# ModulatedIRSensor.net
KiCad netlist of a schematic drawn in EAGLE
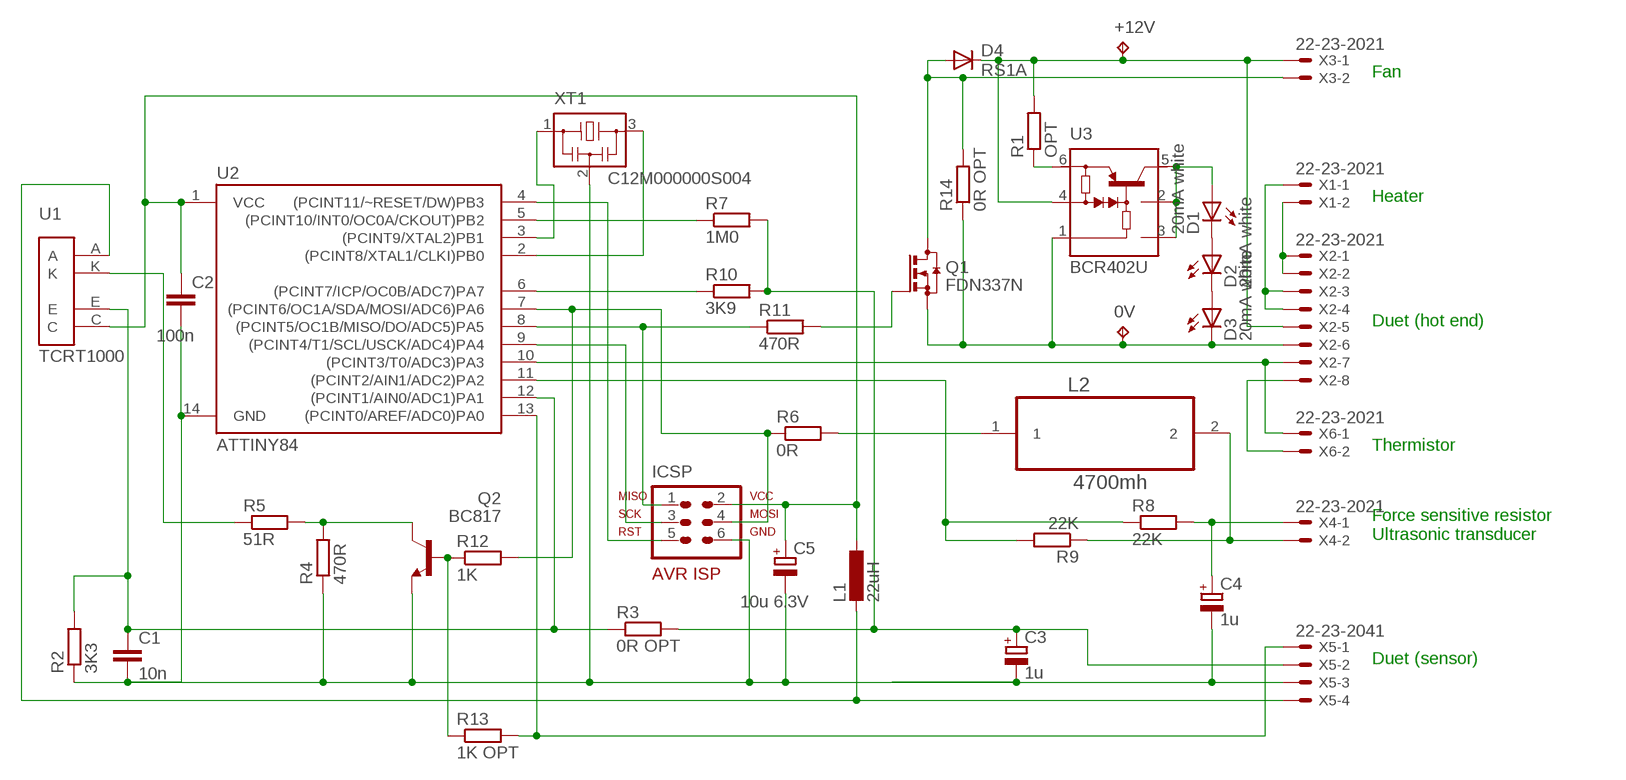
[diagram p0: schematic, sheet 1]

(export (version "E")
  (design (tool "Eeschema 10.0.6"))
  (components
    (comp (ref "+12V")
      (value "TPPAD1-13")
      (footprint "eagle-import:P1-13")
      (libsource (lib "eagle-import") (part "TPPAD1-13"))
    )
    (comp (ref "0V")
      (value "TPPAD1-13")
      (footprint "eagle-import:P1-13")
      (libsource (lib "eagle-import") (part "TPPAD1-13"))
    )
    (comp (ref "C1")
      (value "10n")
      (footprint "eagle-import:C0603")
      (libsource (lib "eagle-import") (part "C-EUC0603"))
    )
    (comp (ref "C2")
      (value "100n")
      (footprint "eagle-import:C0603")
      (libsource (lib "eagle-import") (part "C-EUC0603"))
    )
    (comp (ref "C3")
      (value "1u")
      (footprint "eagle-import:SMC_A")
      (libsource (lib "eagle-import") (part "resistor_CPOL-EUSMCA"))
    )
    (comp (ref "C4")
      (value "1u")
      (footprint "eagle-import:SMC_A")
      (libsource (lib "eagle-import") (part "resistor_CPOL-EUSMCA"))
    )
    (comp (ref "C5")
      (value "10u 6.3V")
      (footprint "eagle-import:SMC_A")
      (libsource (lib "eagle-import") (part "CPOL-EUSMCA"))
    )
    (comp (ref "D1")
      (value "20mA white")
      (footprint "eagle-import:LED5MM")
      (libsource (lib "eagle-import") (part "LED5MM"))
    )
    (comp (ref "D2")
      (value "20mA white")
      (footprint "eagle-import:LED5MM")
      (libsource (lib "eagle-import") (part "LED5MM"))
    )
    (comp (ref "D3")
      (value "20mA white")
      (footprint "eagle-import:LED5MM")
      (libsource (lib "eagle-import") (part "LED5MM"))
    )
    (comp (ref "D4")
      (value "RS1A")
      (footprint "eagle-import:DO214AC")
      (libsource (lib "eagle-import") (part "DIODE-DO214AC"))
    )
    (comp (ref "ICSP")
      (value "AVR-ISP-6VERT")
      (footprint "eagle-import:AVR-ISP-6")
      (libsource (lib "eagle-import") (part "AVR-ISP-6VERT"))
    )
    (comp (ref "L1")
      (value "22uH")
      (footprint "eagle-import:L2012C")
      (libsource (lib "eagle-import") (part "L-EUL2012C"))
    )
    (comp (ref "L2")
      (value "4700mh")
      (footprint "eagle-import:INDC5650X530N")
      (fields (field (name "MPN") "B82442H1475K") (field (name "TOLERANCE") "±10%"))
      (libsource (lib "eagle-import") (part "B82442H1475K"))
    )
    (comp (ref "Q1")
      (value "FDN337N")
      (footprint "eagle-import:SOT23")
      (libsource (lib "eagle-import") (part "BSS123"))
    )
    (comp (ref "Q2")
      (value "BC817")
      (footprint "eagle-import:SOT23")
      (libsource (lib "eagle-import") (part "BC847"))
    )
    (comp (ref "R1")
      (value "OPT")
      (footprint "eagle-import:R0603")
      (libsource (lib "eagle-import") (part "R-EU_R0603"))
    )
    (comp (ref "R2")
      (value "3K3")
      (footprint "eagle-import:R0603")
      (libsource (lib "eagle-import") (part "R-EU_R0603"))
    )
    (comp (ref "R3")
      (value "0R OPT")
      (footprint "eagle-import:R0603")
      (libsource (lib "eagle-import") (part "R-EU_R0603"))
    )
    (comp (ref "R4")
      (value "470R")
      (footprint "eagle-import:R0603")
      (libsource (lib "eagle-import") (part "R-EU_R0603"))
    )
    (comp (ref "R5")
      (value "51R")
      (footprint "eagle-import:R0603")
      (libsource (lib "eagle-import") (part "R-EU_R0603"))
    )
    (comp (ref "R6")
      (value "0R")
      (footprint "eagle-import:R0603")
      (libsource (lib "eagle-import") (part "R-EU_R0603"))
    )
    (comp (ref "R7")
      (value "1M0")
      (footprint "eagle-import:R0603")
      (libsource (lib "eagle-import") (part "R-EU_R0603"))
    )
    (comp (ref "R8")
      (value "22K")
      (footprint "eagle-import:R0603")
      (libsource (lib "eagle-import") (part "R-EU_R0603"))
    )
    (comp (ref "R9")
      (value "22K")
      (footprint "eagle-import:R0603")
      (libsource (lib "eagle-import") (part "R-EU_R0603"))
    )
    (comp (ref "R10")
      (value "3K9")
      (footprint "eagle-import:R0603")
      (libsource (lib "eagle-import") (part "R-EU_R0603"))
    )
    (comp (ref "R11")
      (value "470R")
      (footprint "eagle-import:R0603")
      (libsource (lib "eagle-import") (part "R-EU_R0603"))
    )
    (comp (ref "R12")
      (value "1K")
      (footprint "eagle-import:R0603")
      (libsource (lib "eagle-import") (part "R-EU_R0603"))
    )
    (comp (ref "R13")
      (value "1K OPT")
      (footprint "eagle-import:R0603")
      (libsource (lib "eagle-import") (part "R-EU_R0603"))
    )
    (comp (ref "R14")
      (value "0R OPT")
      (footprint "eagle-import:R0603")
      (libsource (lib "eagle-import") (part "R-EU_R0603"))
    )
    (comp (ref "U1")
      (value "TCRT1000")
      (footprint "eagle-import:TCRT1000")
      (libsource (lib "eagle-import") (part "TCRT1000"))
    )
    (comp (ref "U2")
      (value "ATTINY84")
      (footprint "eagle-import:SO14")
      (libsource (lib "eagle-import") (part "ATTINY84"))
    )
    (comp (ref "U3")
      (value "BCR402U")
      (footprint "eagle-import:SC74_INFINEON")
      (libsource (lib "eagle-import") (part "BCR402U"))
    )
    (comp (ref "X1")
      (value "22-23-2021")
      (footprint "eagle-import:22-23-2021")
      (fields (field (name "MF") "MOLEX"))
      (libsource (lib "eagle-import") (part "22-23-2021"))
    )
    (comp (ref "X2")
      (value "22-23-2021")
      (footprint "eagle-import:22-23-2081")
      (fields (field (name "MF") "MOLEX") (field (name "MPN") "22-23-2081"))
      (libsource (lib "eagle-import") (part "22-23-2081"))
    )
    (comp (ref "X3")
      (value "22-23-2021")
      (footprint "eagle-import:22-23-2021")
      (fields (field (name "MF") "MOLEX"))
      (libsource (lib "eagle-import") (part "22-23-2021"))
    )
    (comp (ref "X4")
      (value "22-23-2021")
      (footprint "eagle-import:22-23-2021")
      (fields (field (name "MF") "MOLEX"))
      (libsource (lib "eagle-import") (part "22-23-2021"))
    )
    (comp (ref "X5")
      (value "22-23-2041")
      (footprint "eagle-import:22-23-2041")
      (fields (field (name "MF") "MOLEX"))
      (libsource (lib "eagle-import") (part "22-23-2041"))
    )
    (comp (ref "X6")
      (value "22-23-2021")
      (footprint "eagle-import:22-23-2021")
      (fields (field (name "MF") "MOLEX"))
      (libsource (lib "eagle-import") (part "22-23-2021"))
    )
    (comp (ref "XT1")
      (value "C12M000000S004")
      (footprint "eagle-import:CSTCR6M")
      (fields (field (name "MPN") "CSTCR6M00G53-R0"))
      (libsource (lib "eagle-import") (part "CSTCR6M00G53Z"))
    )
  )
  (nets
    (net (code "1") (name "Net-(D1-C)") (class "Default")
      (node (ref "D1") (pin "K") (pinfunction "C_K") (pintype "passive"))
      (node (ref "D2") (pin "A") (pinfunction "A_A") (pintype "passive"))
    )
    (net (code "2") (name "Net-(D2-C)") (class "Default")
      (node (ref "D2") (pin "K") (pinfunction "C_K") (pintype "passive"))
      (node (ref "D3") (pin "A") (pinfunction "A_A") (pintype "passive"))
    )
    (net (code "3") (name "Net-(D3-C)") (class "Default")
      (node (ref "0V") (pin "TP") (pinfunction "TP_TP") (pintype "input"))
      (node (ref "D3") (pin "K") (pinfunction "C_K") (pintype "passive"))
      (node (ref "Q1") (pin "2") (pinfunction "S_2") (pintype "passive"))
      (node (ref "R14") (pin "1") (pinfunction "1_1") (pintype "passive"))
      (node (ref "U3") (pin "1") (pinfunction "GND_1") (pintype "power_in"))
      (node (ref "X2") (pin "6") (pinfunction "S_6") (pintype "passive"))
    )
    (net (code "4") (name "Net-(L2-Pad1)") (class "Default")
      (node (ref "L2") (pin "1") (pinfunction "1_1") (pintype "passive"))
      (node (ref "R6") (pin "2") (pinfunction "2_2") (pintype "passive"))
    )
    (net (code "5") (name "Net-(Q1-D)") (class "Default")
      (node (ref "D4") (pin "A") (pinfunction "A_A") (pintype "passive"))
      (node (ref "Q1") (pin "3") (pinfunction "D_3") (pintype "passive"))
      (node (ref "R14") (pin "2") (pinfunction "2_2") (pintype "passive"))
      (node (ref "X3") (pin "2") (pinfunction "S_2") (pintype "passive"))
    )
    (net (code "6") (name "Net-(Q1-G)") (class "Default")
      (node (ref "Q1") (pin "1") (pinfunction "G_1") (pintype "passive"))
      (node (ref "R11") (pin "2") (pinfunction "2_2") (pintype "passive"))
    )
    (net (code "7") (name "Net-(Q2-B)") (class "Default")
      (node (ref "Q2") (pin "1") (pinfunction "B_1") (pintype "passive"))
      (node (ref "R12") (pin "1") (pinfunction "1_1") (pintype "passive"))
      (node (ref "R13") (pin "1") (pinfunction "1_1") (pintype "passive"))
    )
    (net (code "8") (name "Net-(Q2-C)") (class "Default")
      (node (ref "Q2") (pin "3") (pinfunction "C_3") (pintype "passive"))
      (node (ref "R4") (pin "2") (pinfunction "2_2") (pintype "passive"))
      (node (ref "R5") (pin "2") (pinfunction "2_2") (pintype "passive"))
    )
    (net (code "9") (name "Net-(Q2-E)") (class "Default")
      (node (ref "C1") (pin "2") (pinfunction "2_2") (pintype "passive"))
      (node (ref "C2") (pin "2") (pinfunction "2_2") (pintype "passive"))
      (node (ref "C3") (pin "-") (pinfunction "-_-") (pintype "passive"))
      (node (ref "C4") (pin "-") (pinfunction "-_-") (pintype "passive"))
      (node (ref "C5") (pin "-") (pinfunction "-_-") (pintype "passive"))
      (node (ref "ICSP") (pin "6") (pinfunction "6_6") (pintype "passive"))
      (node (ref "Q2") (pin "2") (pinfunction "E_2") (pintype "passive"))
      (node (ref "R2") (pin "1") (pinfunction "1_1") (pintype "passive"))
      (node (ref "R4") (pin "1") (pinfunction "1_1") (pintype "passive"))
      (node (ref "U2") (pin "14") (pinfunction "GND_14") (pintype "bidirectional"))
      (node (ref "X5") (pin "3") (pinfunction "S_3") (pintype "passive"))
      (node (ref "XT1") (pin "2") (pinfunction "2_2") (pintype "passive"))
    )
    (net (code "10") (name "Net-(R5-Pad1)") (class "Default")
      (node (ref "R5") (pin "1") (pinfunction "1_1") (pintype "passive"))
      (node (ref "U1") (pin "K") (pinfunction "K_K") (pintype "input"))
    )
    (net (code "11") (name "Net-(U2-(PCINT0{slash}AREF{slash}ADC0)PA0)") (class "Default")
      (node (ref "R13") (pin "2") (pinfunction "2_2") (pintype "passive"))
      (node (ref "U2") (pin "13") (pinfunction "(PCINT0/AREF/ADC0)PA0_13") (pintype "bidirectional"))
      (node (ref "X5") (pin "1") (pinfunction "S_1") (pintype "passive"))
    )
    (net (code "12") (name "Net-(U2-(PCINT1{slash}AIN0{slash}ADC1)PA1)") (class "Default")
      (node (ref "C1") (pin "1") (pinfunction "1_1") (pintype "passive"))
      (node (ref "R2") (pin "2") (pinfunction "2_2") (pintype "passive"))
      (node (ref "R3") (pin "1") (pinfunction "1_1") (pintype "passive"))
      (node (ref "U1") (pin "E") (pinfunction "E_E") (pintype "bidirectional"))
      (node (ref "U2") (pin "12") (pinfunction "(PCINT1/AIN0/ADC1)PA1_12") (pintype "bidirectional"))
    )
    (net (code "13") (name "Net-(U2-(PCINT2{slash}AIN1{slash}ADC2)PA2)") (class "Default")
      (node (ref "R8") (pin "1") (pinfunction "1_1") (pintype "passive"))
      (node (ref "R9") (pin "2") (pinfunction "2_2") (pintype "passive"))
      (node (ref "U2") (pin "11") (pinfunction "(PCINT2/AIN1/ADC2)PA2_11") (pintype "bidirectional"))
    )
    (net (code "14") (name "Net-(U2-(PCINT3{slash}T0{slash}ADC3)PA3)") (class "Default")
      (node (ref "U2") (pin "10") (pinfunction "(PCINT3/T0/ADC3)PA3_10") (pintype "bidirectional"))
      (node (ref "X2") (pin "7") (pinfunction "S_7") (pintype "passive"))
      (node (ref "X6") (pin "1") (pinfunction "S_1") (pintype "passive"))
    )
    (net (code "15") (name "Net-(U2-(PCINT4{slash}T1{slash}SCL{slash}USCK{slash}ADC4)PA4)") (class "Default")
      (node (ref "ICSP") (pin "3") (pinfunction "3_3") (pintype "passive"))
      (node (ref "U2") (pin "9") (pinfunction "(PCINT4/T1/SCL/USCK/ADC4)PA4_9") (pintype "bidirectional"))
    )
    (net (code "16") (name "Net-(U2-(PCINT5{slash}OC1B{slash}MISO{slash}DO{slash}ADC5)PA5)") (class "Default")
      (node (ref "ICSP") (pin "1") (pinfunction "1_1") (pintype "passive"))
      (node (ref "R11") (pin "1") (pinfunction "1_1") (pintype "passive"))
      (node (ref "U2") (pin "8") (pinfunction "(PCINT5/OC1B/MISO/DO/ADC5)PA5_8") (pintype "bidirectional"))
    )
    (net (code "17") (name "Net-(U2-(PCINT6{slash}OC1A{slash}SDA{slash}MOSI{slash}ADC6)PA6)") (class "Default")
      (node (ref "ICSP") (pin "4") (pinfunction "4_4") (pintype "passive"))
      (node (ref "R12") (pin "2") (pinfunction "2_2") (pintype "passive"))
      (node (ref "R6") (pin "1") (pinfunction "1_1") (pintype "passive"))
      (node (ref "U2") (pin "7") (pinfunction "(PCINT6/OC1A/SDA/MOSI/ADC6)PA6_7") (pintype "bidirectional"))
    )
    (net (code "18") (name "Net-(U2-(PCINT7{slash}ICP{slash}OC0B{slash}ADC7)PA7)") (class "Default")
      (node (ref "R10") (pin "1") (pinfunction "1_1") (pintype "passive"))
      (node (ref "U2") (pin "6") (pinfunction "(PCINT7/ICP/OC0B/ADC7)PA7_6") (pintype "bidirectional"))
    )
    (net (code "19") (name "Net-(U2-(PCINT8{slash}XTAL1{slash}CLKI)PB0)") (class "Default")
      (node (ref "U2") (pin "2") (pinfunction "(PCINT8/XTAL1/CLKI)PB0_2") (pintype "bidirectional"))
      (node (ref "XT1") (pin "3") (pinfunction "3_3") (pintype "passive"))
    )
    (net (code "20") (name "Net-(U2-(PCINT9{slash}XTAL2)PB1)") (class "Default")
      (node (ref "U2") (pin "3") (pinfunction "(PCINT9/XTAL2)PB1_3") (pintype "bidirectional"))
      (node (ref "XT1") (pin "1") (pinfunction "1_1") (pintype "passive"))
    )
    (net (code "21") (name "Net-(U2-(PCINT10{slash}INT0{slash}OC0A{slash}CKOUT)PB2)") (class "Default")
      (node (ref "R7") (pin "1") (pinfunction "1_1") (pintype "passive"))
      (node (ref "U2") (pin "5") (pinfunction "(PCINT10/INT0/OC0A/CKOUT)PB2_5") (pintype "bidirectional"))
    )
    (net (code "22") (name "Net-(U2-(PCINT11{slash}~{RESET{slash}DW})PB3)") (class "Default")
      (node (ref "ICSP") (pin "5") (pinfunction "5_5") (pintype "passive"))
      (node (ref "U2") (pin "4") (pinfunction "(PCINT11/~{RESET/DW})PB3_4") (pintype "bidirectional"))
    )
    (net (code "23") (name "Net-(U2-VCC)") (class "Default")
      (node (ref "C2") (pin "1") (pinfunction "1_1") (pintype "passive"))
      (node (ref "C5") (pin "+") (pinfunction "+_+") (pintype "passive"))
      (node (ref "ICSP") (pin "2") (pinfunction "2_2") (pintype "passive"))
      (node (ref "L1") (pin "1") (pinfunction "1_1") (pintype "passive"))
      (node (ref "U1") (pin "C") (pinfunction "C_C") (pintype "bidirectional"))
      (node (ref "U2") (pin "1") (pinfunction "VCC_1") (pintype "bidirectional"))
    )
    (net (code "24") (name "Net-(U3-IOUT1)") (class "Default")
      (node (ref "D1") (pin "A") (pinfunction "A_A") (pintype "passive"))
      (node (ref "U3") (pin "2") (pinfunction "IOUT2_2") (pintype "open_collector"))
      (node (ref "U3") (pin "3") (pinfunction "IOUT3_3") (pintype "open_collector"))
      (node (ref "U3") (pin "5") (pinfunction "IOUT1_5") (pintype "open_collector"))
    )
    (net (code "25") (name "Net-(U3-REXT)") (class "Default")
      (node (ref "R1") (pin "1") (pinfunction "1_1") (pintype "passive"))
      (node (ref "U3") (pin "6") (pinfunction "REXT_6") (pintype "input"))
    )
    (net (code "26") (name "Net-(U3-VIN)") (class "Default")
      (node (ref "+12V") (pin "TP") (pinfunction "TP_TP") (pintype "input"))
      (node (ref "D4") (pin "C") (pinfunction "C_C") (pintype "passive"))
      (node (ref "R1") (pin "2") (pinfunction "2_2") (pintype "passive"))
      (node (ref "U3") (pin "4") (pinfunction "VIN_4") (pintype "power_in"))
      (node (ref "X2") (pin "5") (pinfunction "S_5") (pintype "passive"))
      (node (ref "X3") (pin "1") (pinfunction "S_1") (pintype "passive"))
    )
    (net (code "27") (name "Net-(X1A-S)") (class "Default")
      (node (ref "X1") (pin "1") (pinfunction "S_1") (pintype "passive"))
      (node (ref "X2") (pin "3") (pinfunction "S_3") (pintype "passive"))
      (node (ref "X2") (pin "4") (pinfunction "S_4") (pintype "passive"))
    )
    (net (code "28") (name "Net-(X1B-S)") (class "Default")
      (node (ref "X1") (pin "2") (pinfunction "S_2") (pintype "passive"))
      (node (ref "X2") (pin "1") (pinfunction "S_1") (pintype "passive"))
      (node (ref "X2") (pin "2") (pinfunction "S_2") (pintype "passive"))
    )
    (net (code "29") (name "Net-(X2H-S)") (class "Default")
      (node (ref "X2") (pin "8") (pinfunction "S_8") (pintype "passive"))
      (node (ref "X6") (pin "2") (pinfunction "S_2") (pintype "passive"))
    )
    (net (code "30") (name "Net-(X4A-S)") (class "Default")
      (node (ref "C4") (pin "+") (pinfunction "+_+") (pintype "passive"))
      (node (ref "R8") (pin "2") (pinfunction "2_2") (pintype "passive"))
      (node (ref "X4") (pin "1") (pinfunction "S_1") (pintype "passive"))
    )
    (net (code "31") (name "Net-(X4B-S)") (class "Default")
      (node (ref "L2") (pin "2") (pinfunction "2_2") (pintype "passive"))
      (node (ref "R9") (pin "1") (pinfunction "1_1") (pintype "passive"))
      (node (ref "X4") (pin "2") (pinfunction "S_2") (pintype "passive"))
    )
    (net (code "32") (name "Net-(X5B-S)") (class "Default")
      (node (ref "C3") (pin "+") (pinfunction "+_+") (pintype "passive"))
      (node (ref "R10") (pin "2") (pinfunction "2_2") (pintype "passive"))
      (node (ref "R3") (pin "2") (pinfunction "2_2") (pintype "passive"))
      (node (ref "R7") (pin "2") (pinfunction "2_2") (pintype "passive"))
      (node (ref "X5") (pin "2") (pinfunction "S_2") (pintype "passive"))
    )
    (net (code "33") (name "Net-(X5D-S)") (class "Default")
      (node (ref "L1") (pin "2") (pinfunction "2_2") (pintype "passive"))
      (node (ref "U1") (pin "A") (pinfunction "A_A") (pintype "input"))
      (node (ref "X5") (pin "4") (pinfunction "S_4") (pintype "passive"))
    )
  )
)
